# ledPower.net
KiCad netlist of a schematic drawn in EAGLE
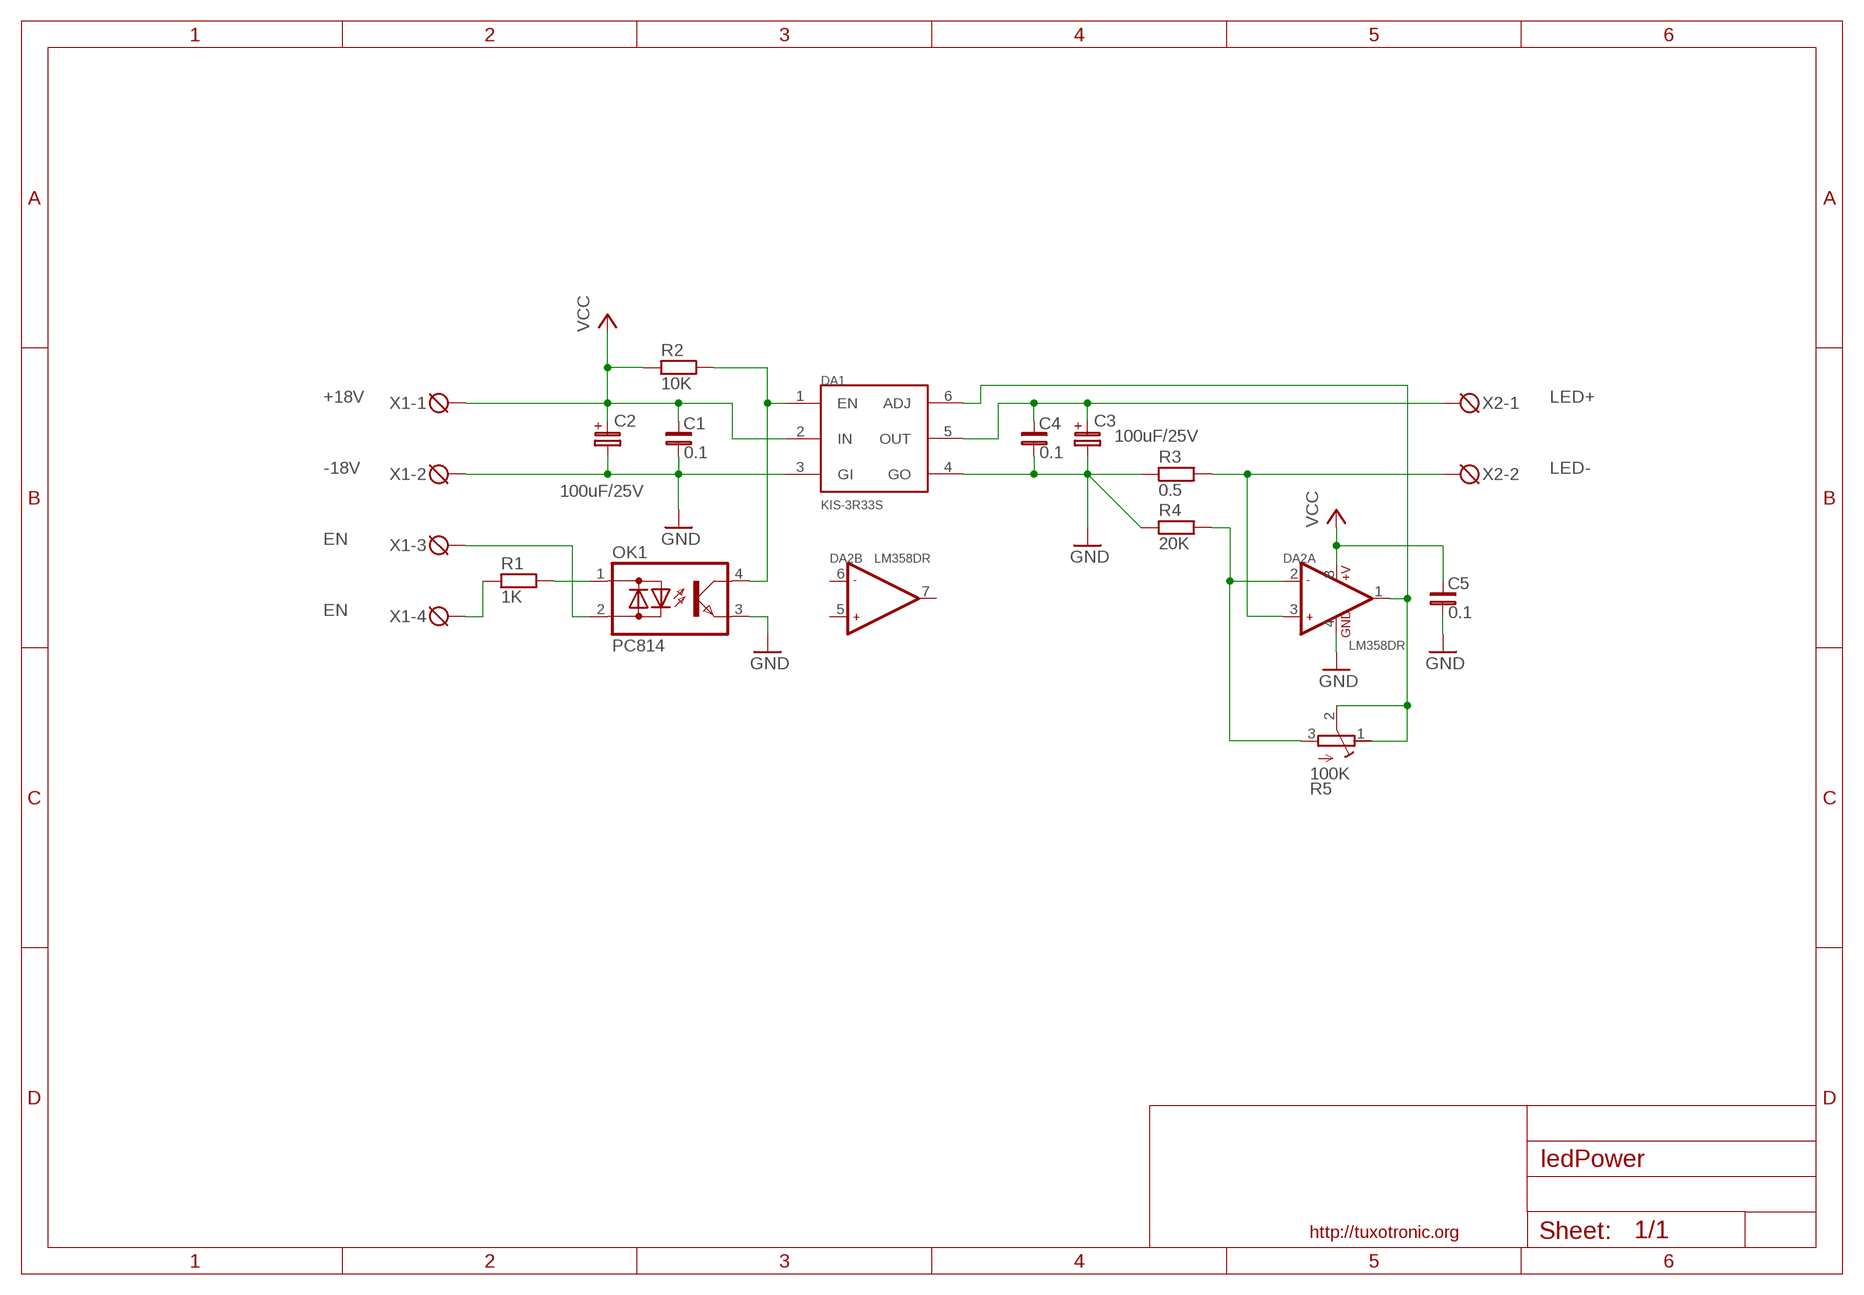
[diagram p0: schematic, sheet 1]

(export (version "E")
  (design (tool "Eeschema 10.0.6"))
  (components
    (comp (ref "C1")
      (value "0.1")
      (footprint "eagle-import:C1206")
      (libsource (lib "eagle-import") (part "C_1206"))
    )
    (comp (ref "C2")
      (value "100uF/25V")
      (footprint "eagle-import:CE-025X060")
      (libsource (lib "eagle-import") (part "CP_E-025X060"))
    )
    (comp (ref "C3")
      (value "100uF/25V")
      (footprint "eagle-import:CE-025X060")
      (libsource (lib "eagle-import") (part "CP_E-025X060"))
    )
    (comp (ref "C4")
      (value "0.1")
      (footprint "eagle-import:C1206")
      (libsource (lib "eagle-import") (part "C_1206"))
    )
    (comp (ref "C5")
      (value "0.1")
      (footprint "eagle-import:C0805")
      (libsource (lib "eagle-import") (part "C_0805"))
    )
    (comp (ref "DA1")
      (value "KIS-3R33S")
      (footprint "eagle-import:KIS-3R33S")
      (libsource (lib "eagle-import") (part "KIS-3R33S"))
    )
    (comp (ref "DA2")
      (value "LM358DR")
      (footprint "eagle-import:SOIC8")
      (libsource (lib "eagle-import") (part "LM358DR-1110010P1"))
    )
    (comp (ref "OK1")
      (value "PC814")
      (footprint "eagle-import:DIL04")
      (libsource (lib "eagle-import") (part "PC814"))
    )
    (comp (ref "R1")
      (value "1K")
      (footprint "eagle-import:R0805")
      (libsource (lib "eagle-import") (part "R_0805"))
    )
    (comp (ref "R2")
      (value "10K")
      (footprint "eagle-import:R0805")
      (libsource (lib "eagle-import") (part "R_0805"))
    )
    (comp (ref "R3")
      (value "0.5")
      (footprint "eagle-import:0414_15")
      (libsource (lib "eagle-import") (part "R_X0414/15"))
    )
    (comp (ref "R4")
      (value "20K")
      (footprint "eagle-import:R0805")
      (libsource (lib "eagle-import") (part "R_0805"))
    )
    (comp (ref "R5")
      (value "100K")
      (footprint "eagle-import:RTRIMT93YA")
      (libsource (lib "eagle-import") (part "R-TRIMMT93YA"))
    )
    (comp (ref "X1")
      (value "DG3XX-04-0.5")
      (footprint "eagle-import:DG306-5.0-04P")
      (libsource (lib "eagle-import") (part "DG3XX-04-0.5"))
    )
    (comp (ref "X2")
      (value "DG3XX-02-5.0")
      (footprint "eagle-import:DG306-5.0-02P")
      (libsource (lib "eagle-import") (part "DG3XX-02-5.0"))
    )
  )
  (nets
    (net (code "1") (name "GND") (class "Default")
      (node (ref "C1") (pin "2") (pinfunction "2_2") (pintype "passive"))
      (node (ref "C2") (pin "-") (pinfunction "-_-") (pintype "passive"))
      (node (ref "C3") (pin "-") (pinfunction "-_-") (pintype "passive"))
      (node (ref "C4") (pin "2") (pinfunction "2_2") (pintype "passive"))
      (node (ref "C5") (pin "2") (pinfunction "2_2") (pintype "passive"))
      (node (ref "DA1") (pin "3") (pinfunction "GI_3") (pintype "power_in"))
      (node (ref "DA1") (pin "4") (pinfunction "GO_4") (pintype "power_in"))
      (node (ref "DA2") (pin "4") (pinfunction "GND_4") (pintype "power_in"))
      (node (ref "OK1") (pin "3") (pinfunction "E_3") (pintype "passive"))
      (node (ref "R3") (pin "1") (pinfunction "1_1") (pintype "passive"))
      (node (ref "R4") (pin "1") (pinfunction "1_1") (pintype "passive"))
      (node (ref "X1") (pin "2") (pinfunction "KL_2") (pintype "passive"))
    )
    (net (code "2") (name "Net-(DA1-ADJ)") (class "Default")
      (node (ref "DA1") (pin "6") (pinfunction "ADJ_6") (pintype "bidirectional"))
      (node (ref "DA2") (pin "1") (pinfunction "OUT1_1") (pintype "output"))
      (node (ref "R5") (pin "1") (pinfunction "A_1") (pintype "passive"))
      (node (ref "R5") (pin "2") (pinfunction "S_2") (pintype "passive"))
    )
    (net (code "3") (name "Net-(DA1-EN)") (class "Default")
      (node (ref "DA1") (pin "1") (pinfunction "EN_1") (pintype "bidirectional"))
      (node (ref "OK1") (pin "4") (pinfunction "C_4") (pintype "passive"))
      (node (ref "R2") (pin "2") (pinfunction "2_2") (pintype "passive"))
    )
    (net (code "4") (name "Net-(DA1-OUT)") (class "Default")
      (node (ref "C3") (pin "+") (pinfunction "+_+") (pintype "passive"))
      (node (ref "C4") (pin "1") (pinfunction "1_1") (pintype "passive"))
      (node (ref "DA1") (pin "5") (pinfunction "OUT_5") (pintype "bidirectional"))
      (node (ref "X2") (pin "1") (pinfunction "KL_1") (pintype "passive"))
    )
    (net (code "5") (name "Net-(DA2A-+IN1)") (class "Default")
      (node (ref "DA2") (pin "3") (pinfunction "+IN1_3") (pintype "input"))
      (node (ref "R3") (pin "2") (pinfunction "2_2") (pintype "passive"))
      (node (ref "X2") (pin "2") (pinfunction "KL_2") (pintype "passive"))
    )
    (net (code "6") (name "Net-(DA2A--IN1)") (class "Default")
      (node (ref "DA2") (pin "2") (pinfunction "-IN1_2") (pintype "input"))
      (node (ref "R4") (pin "2") (pinfunction "2_2") (pintype "passive"))
      (node (ref "R5") (pin "3") (pinfunction "E_3") (pintype "passive"))
    )
    (net (code "7") (name "Net-(OK1-AC1)") (class "Default")
      (node (ref "OK1") (pin "1") (pinfunction "AC1_1") (pintype "passive"))
      (node (ref "R1") (pin "2") (pinfunction "2_2") (pintype "passive"))
    )
    (net (code "8") (name "Net-(OK1-AC2)") (class "Default")
      (node (ref "OK1") (pin "2") (pinfunction "AC2_2") (pintype "passive"))
      (node (ref "X1") (pin "3") (pinfunction "KL_3") (pintype "passive"))
    )
    (net (code "9") (name "Net-(X1D-KL)") (class "Default")
      (node (ref "R1") (pin "1") (pinfunction "1_1") (pintype "passive"))
      (node (ref "X1") (pin "4") (pinfunction "KL_4") (pintype "passive"))
    )
    (net (code "10") (name "VCC") (class "Default")
      (node (ref "C1") (pin "1") (pinfunction "1_1") (pintype "passive"))
      (node (ref "C2") (pin "+") (pinfunction "+_+") (pintype "passive"))
      (node (ref "C5") (pin "1") (pinfunction "1_1") (pintype "passive"))
      (node (ref "DA1") (pin "2") (pinfunction "IN_2") (pintype "bidirectional"))
      (node (ref "DA2") (pin "8") (pinfunction "+V_8") (pintype "power_in"))
      (node (ref "R2") (pin "1") (pinfunction "1_1") (pintype "passive"))
      (node (ref "X1") (pin "1") (pinfunction "KL_1") (pintype "passive"))
    )
    (net (code "11") (name "unconnected-(DA2B-+IN2-Pad5)") (class "Default")
      (node (ref "DA2") (pin "5") (pinfunction "+IN2_5") (pintype "input"))
    )
    (net (code "12") (name "unconnected-(DA2B--IN2-Pad6)") (class "Default")
      (node (ref "DA2") (pin "6") (pinfunction "-IN2_6") (pintype "input"))
    )
    (net (code "13") (name "unconnected-(DA2B-OUT2-Pad7)") (class "Default")
      (node (ref "DA2") (pin "7") (pinfunction "OUT2_7") (pintype "output"))
    )
  )
)
